# ControllerV1.net
KiCad netlist of a schematic drawn in Altium Designer
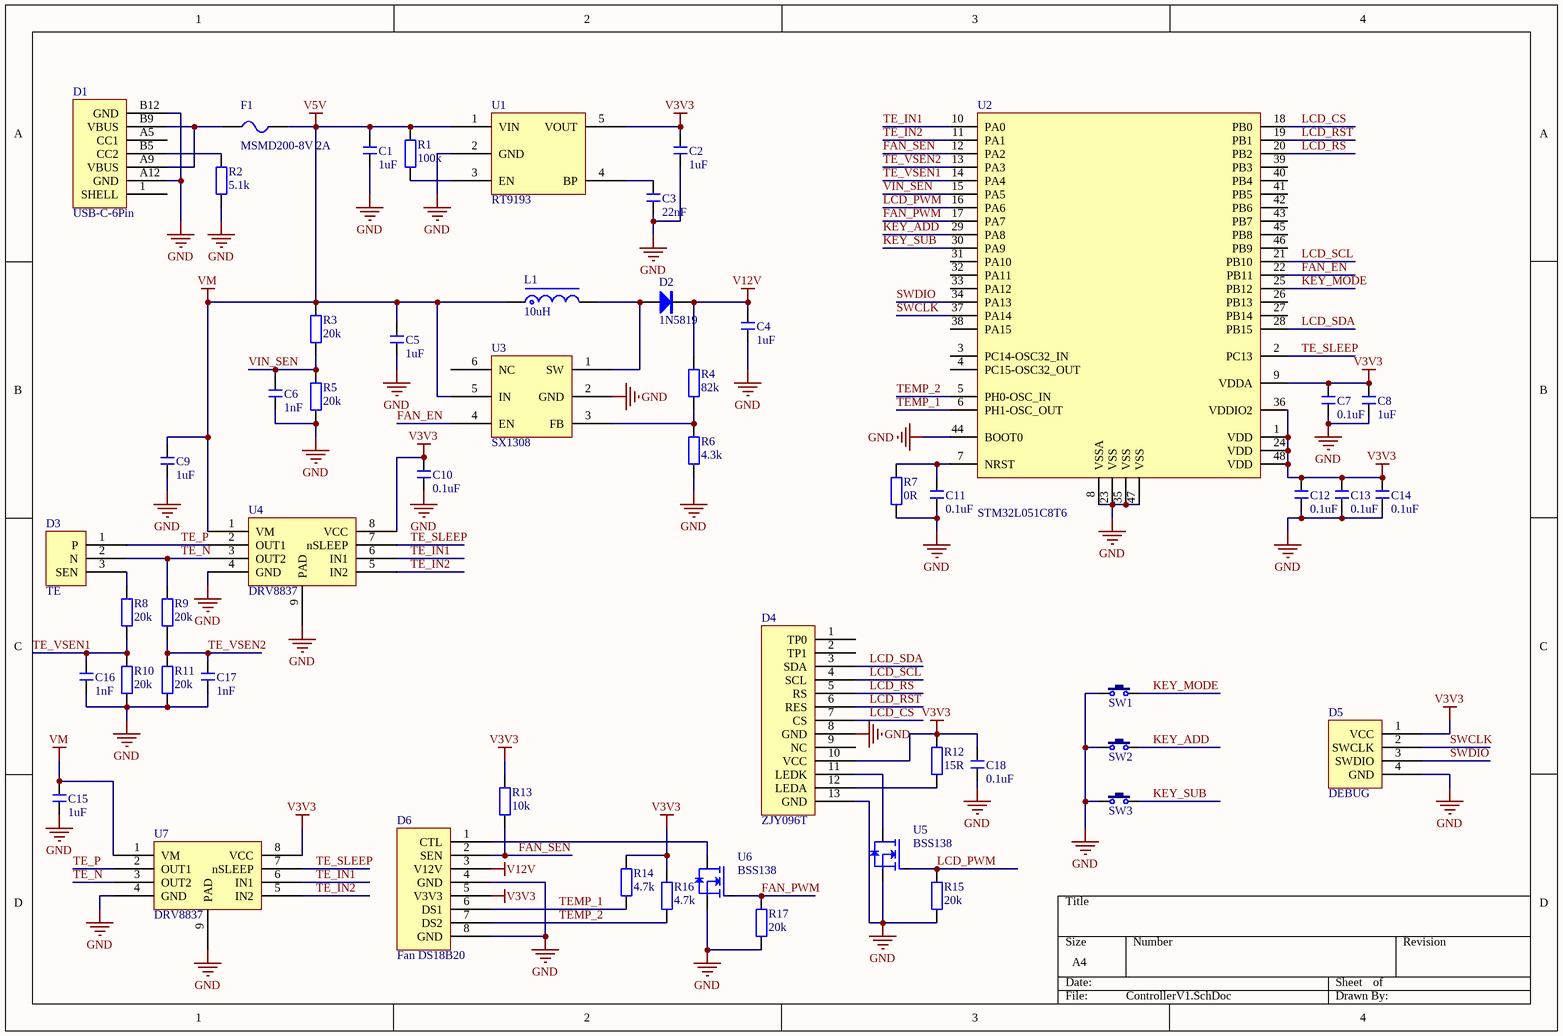
[diagram p0: ControllerV1.SchDoc]

(export (version "E")
  (design (tool "Eeschema 10.0.6"))
  (components
    (comp (ref "C1")
      (value "1uF")
      (footprint "C 0603_L")
      (description "无极性贴片电容")
      (fields (field (name "版权归属") "源创客"))
      (libsource (lib "3.1   - 电阻-电容-电感") (part "C"))
    )
    (comp (ref "C2")
      (value "1uF")
      (footprint "C 0603_L")
      (description "无极性贴片电容")
      (fields (field (name "版权归属") "源创客"))
      (libsource (lib "3.1   - 电阻-电容-电感") (part "C"))
    )
    (comp (ref "C3")
      (value "22nF")
      (footprint "C 0603_L")
      (description "无极性贴片电容")
      (fields (field (name "版权归属") "源创客"))
      (libsource (lib "3.1   - 电阻-电容-电感") (part "C"))
    )
    (comp (ref "C4")
      (value "1uF")
      (footprint "C 0603_L")
      (description "无极性贴片电容")
      (fields (field (name "版权归属") "源创客"))
      (libsource (lib "3.1   - 电阻-电容-电感") (part "C"))
    )
    (comp (ref "C5")
      (value "1uF")
      (footprint "C 0603_L")
      (description "无极性贴片电容")
      (fields (field (name "版权归属") "源创客"))
      (libsource (lib "3.1   - 电阻-电容-电感") (part "C"))
    )
    (comp (ref "C6")
      (value "1nF")
      (footprint "C 0603_L")
      (description "无极性贴片电容")
      (fields (field (name "版权归属") "源创客"))
      (libsource (lib "3.1   - 电阻-电容-电感") (part "C"))
    )
    (comp (ref "C7")
      (value "0.1uF")
      (footprint "C 0603_L")
      (description "无极性贴片电容")
      (fields (field (name "版权归属") "源创客"))
      (libsource (lib "3.1   - 电阻-电容-电感") (part "C"))
    )
    (comp (ref "C8")
      (value "1uF")
      (footprint "C 0603_L")
      (description "无极性贴片电容")
      (fields (field (name "版权归属") "源创客"))
      (libsource (lib "3.1   - 电阻-电容-电感") (part "C"))
    )
    (comp (ref "C9")
      (value "1uF")
      (footprint "C 0603_L")
      (description "无极性贴片电容")
      (fields (field (name "版权归属") "源创客"))
      (libsource (lib "3.1   - 电阻-电容-电感") (part "C"))
    )
    (comp (ref "C10")
      (value "0.1uF")
      (footprint "C 0603_L")
      (description "无极性贴片电容")
      (fields (field (name "版权归属") "源创客"))
      (libsource (lib "3.1   - 电阻-电容-电感") (part "C"))
    )
    (comp (ref "C11")
      (value "0.1uF")
      (footprint "C 0603_L")
      (description "无极性贴片电容")
      (fields (field (name "版权归属") "源创客"))
      (libsource (lib "3.1   - 电阻-电容-电感") (part "C"))
    )
    (comp (ref "C12")
      (value "0.1uF")
      (footprint "C 0603_L")
      (description "无极性贴片电容")
      (fields (field (name "版权归属") "源创客"))
      (libsource (lib "3.1   - 电阻-电容-电感") (part "C"))
    )
    (comp (ref "C13")
      (value "0.1uF")
      (footprint "C 0603_L")
      (description "无极性贴片电容")
      (fields (field (name "版权归属") "源创客"))
      (libsource (lib "3.1   - 电阻-电容-电感") (part "C"))
    )
    (comp (ref "C14")
      (value "0.1uF")
      (footprint "C 0603_L")
      (description "无极性贴片电容")
      (fields (field (name "版权归属") "源创客"))
      (libsource (lib "3.1   - 电阻-电容-电感") (part "C"))
    )
    (comp (ref "C15")
      (value "1uF")
      (footprint "C 0603_L")
      (description "无极性贴片电容")
      (fields (field (name "版权归属") "源创客"))
      (libsource (lib "3.1   - 电阻-电容-电感") (part "C"))
    )
    (comp (ref "C16")
      (value "1nF")
      (footprint "C 0603_L")
      (description "无极性贴片电容")
      (fields (field (name "版权归属") "源创客"))
      (libsource (lib "3.1   - 电阻-电容-电感") (part "C"))
    )
    (comp (ref "C17")
      (value "1nF")
      (footprint "C 0603_L")
      (description "无极性贴片电容")
      (fields (field (name "版权归属") "源创客"))
      (libsource (lib "3.1   - 电阻-电容-电感") (part "C"))
    )
    (comp (ref "C18")
      (value "0.1uF")
      (footprint "C 0603_L")
      (description "无极性贴片电容")
      (fields (field (name "版权归属") "源创客"))
      (libsource (lib "3.1   - 电阻-电容-电感") (part "C"))
    )
    (comp (ref "D1")
      (value "USB-C-6Pin")
      (footprint "USB-C-6Pin-InBoard")
      (libsource (lib "AlPcb") (part "USB-C-6Pin"))
    )
    (comp (ref "D2")
      (value "1N5819")
      (footprint "SOD-323")
      (description "肖特基二极管")
      (fields (field (name "版权归属") "源创客"))
      (libsource (lib "8.1   - 二极管-整流桥") (part "1N5819"))
    )
    (comp (ref "D3") (value "TE") (footprint "TE") (libsource (lib "ThermosCupLib") (part "TE")))
    (comp (ref "D4")
      (value "ZJY096T")
      (footprint "LCD_0p96_ZJY096T")
      (libsource (lib "AlPcb") (part "LCD_0p96_ZJY096T"))
    )
    (comp (ref "D5") (value "DEBUG") (footprint "DBG") (libsource (lib "ThermosCupLib") (part "DBG")))
    (comp (ref "D6")
      (value "Fan DS18B20")
      (footprint "Connector Fan DS18B20")
      (libsource (lib "ThermosCupLib") (part "Connecter Fan DS18B20"))
    )
    (comp (ref "F1")
      (value "MSMD200-8V 2A")
      (footprint "FU 1206")
      (description "贴片保险丝")
      (fields (field (name "版权归属") "源创客"))
      (libsource (lib "保险丝-晶振") (part "FU"))
    )
    (comp (ref "L1")
      (value "10uH")
      (footprint "NR4020")
      (description "NR磁胶电感")
      (fields (field (name "版权归属") "源创客"))
      (libsource (lib "3.1   - 电阻-电容-电感") (part "L-NR"))
    )
    (comp (ref "R1")
      (value "100k")
      (footprint "R 0603_L")
      (description "贴片电阻")
      (fields (field (name "版权归属") "源创客"))
      (libsource (lib "3.1   - 电阻-电容-电感") (part "R"))
    )
    (comp (ref "R2")
      (value "5.1k")
      (footprint "R 0603_L")
      (description "贴片电阻")
      (fields (field (name "版权归属") "源创客"))
      (libsource (lib "3.1   - 电阻-电容-电感") (part "R"))
    )
    (comp (ref "R3")
      (value "20k")
      (footprint "R 0603_L")
      (description "贴片电阻")
      (fields (field (name "版权归属") "源创客"))
      (libsource (lib "3.1   - 电阻-电容-电感") (part "R"))
    )
    (comp (ref "R4")
      (value "82k")
      (footprint "R 0603_L")
      (description "贴片电阻")
      (fields (field (name "版权归属") "源创客"))
      (libsource (lib "3.1   - 电阻-电容-电感") (part "R"))
    )
    (comp (ref "R5")
      (value "20k")
      (footprint "R 0603_L")
      (description "贴片电阻")
      (fields (field (name "版权归属") "源创客"))
      (libsource (lib "3.1   - 电阻-电容-电感") (part "R"))
    )
    (comp (ref "R6")
      (value "4.3k")
      (footprint "R 0603_L")
      (description "贴片电阻")
      (fields (field (name "版权归属") "源创客"))
      (libsource (lib "3.1   - 电阻-电容-电感") (part "R"))
    )
    (comp (ref "R7")
      (value "0R")
      (footprint "R 0603_L")
      (description "贴片电阻")
      (fields (field (name "版权归属") "源创客"))
      (libsource (lib "3.1   - 电阻-电容-电感") (part "R"))
    )
    (comp (ref "R8")
      (value "20k")
      (footprint "R 0603_L")
      (description "贴片电阻")
      (fields (field (name "版权归属") "源创客"))
      (libsource (lib "3.1   - 电阻-电容-电感") (part "R"))
    )
    (comp (ref "R9")
      (value "20k")
      (footprint "R 0603_L")
      (description "贴片电阻")
      (fields (field (name "版权归属") "源创客"))
      (libsource (lib "3.1   - 电阻-电容-电感") (part "R"))
    )
    (comp (ref "R10")
      (value "20k")
      (footprint "R 0603_L")
      (description "贴片电阻")
      (fields (field (name "版权归属") "源创客"))
      (libsource (lib "3.1   - 电阻-电容-电感") (part "R"))
    )
    (comp (ref "R11")
      (value "20k")
      (footprint "R 0603_L")
      (description "贴片电阻")
      (fields (field (name "版权归属") "源创客"))
      (libsource (lib "3.1   - 电阻-电容-电感") (part "R"))
    )
    (comp (ref "R12")
      (value "15R")
      (footprint "R 0603_L")
      (description "贴片电阻")
      (fields (field (name "版权归属") "源创客"))
      (libsource (lib "3.1   - 电阻-电容-电感") (part "R"))
    )
    (comp (ref "R13")
      (value "10k")
      (footprint "R 0603_L")
      (description "贴片电阻")
      (fields (field (name "版权归属") "源创客"))
      (libsource (lib "3.1   - 电阻-电容-电感") (part "R"))
    )
    (comp (ref "R14")
      (value "4.7k")
      (footprint "R 0603_L")
      (description "贴片电阻")
      (fields (field (name "版权归属") "源创客"))
      (libsource (lib "3.1   - 电阻-电容-电感") (part "R"))
    )
    (comp (ref "R15")
      (value "20k")
      (footprint "R 0603_L")
      (description "贴片电阻")
      (fields (field (name "版权归属") "源创客"))
      (libsource (lib "3.1   - 电阻-电容-电感") (part "R"))
    )
    (comp (ref "R16")
      (value "4.7k")
      (footprint "R 0603_L")
      (description "贴片电阻")
      (fields (field (name "版权归属") "源创客"))
      (libsource (lib "3.1   - 电阻-电容-电感") (part "R"))
    )
    (comp (ref "R17")
      (value "20k")
      (footprint "R 0603_L")
      (description "贴片电阻")
      (fields (field (name "版权归属") "源创客"))
      (libsource (lib "3.1   - 电阻-电容-电感") (part "R"))
    )
    (comp (ref "SW1")
      (value "3x6x5")
      (footprint "TSW SMD-3*6*5")
      (description "3x6轻触开关")
      (fields (field (name "版权归属") "源创客"))
      (libsource (lib "5.1   - 按键-开关") (part "TSW 3x6"))
    )
    (comp (ref "SW2")
      (value "3x6x5")
      (footprint "TSW SMD-3*6*5")
      (description "3x6轻触开关")
      (fields (field (name "版权归属") "源创客"))
      (libsource (lib "5.1   - 按键-开关") (part "TSW 3x6"))
    )
    (comp (ref "SW3")
      (value "3x6x5")
      (footprint "TSW SMD-3*6*5")
      (description "3x6轻触开关")
      (fields (field (name "版权归属") "源创客"))
      (libsource (lib "5.1   - 按键-开关") (part "TSW 3x6"))
    )
    (comp (ref "U1") (value "RT9193") (footprint "SOT23-5 RT9193") (libsource (lib "AlPcb") (part "RT9193")))
    (comp (ref "U2")
      (value "STM32L051C8T6")
      (footprint "LQFP48")
      (libsource (lib "AlPcb") (part "STM32L051C8T6"))
    )
    (comp (ref "U3") (value "SX1308") (footprint "SOT23-6 SX1308") (libsource (lib "AlPcb") (part "SX1308")))
    (comp (ref "U4")
      (value "DRV8837")
      (footprint "WSON-8 DRV8837")
      (libsource (lib "AlPcb") (part "DRV8837"))
    )
    (comp (ref "U5") (value "BSS138") (footprint "SOT23-3 BSS138") (libsource (lib "AlPcb") (part "BSS138")))
    (comp (ref "U6") (value "BSS138") (footprint "SOT23-3 BSS138") (libsource (lib "AlPcb") (part "BSS138")))
    (comp (ref "U7")
      (value "DRV8837")
      (footprint "WSON-8 DRV8837")
      (libsource (lib "AlPcb") (part "DRV8837"))
    )
  )
  (nets
    (net (code "1") (name "/FAN_EN") (class "Default")
      (node (ref "U2") (pin "22") (pinfunction "PB11_22") (pintype "passive"))
      (node (ref "U3") (pin "4") (pinfunction "EN_4") (pintype "passive"))
    )
    (net (code "2") (name "/FAN_PWM") (class "Default")
      (node (ref "R17") (pin "2") (pinfunction "2_2") (pintype "passive"))
      (node (ref "U2") (pin "17") (pinfunction "PA7_17") (pintype "passive"))
      (node (ref "U6") (pin "1") (pinfunction "G_1") (pintype "passive"))
    )
    (net (code "3") (name "/FAN_SEN") (class "Default")
      (node (ref "D6") (pin "2") (pinfunction "SEN_2") (pintype "passive"))
      (node (ref "R13") (pin "1") (pinfunction "1_1") (pintype "passive"))
      (node (ref "U2") (pin "12") (pinfunction "PA2_12") (pintype "passive"))
    )
    (net (code "4") (name "/KEY_ADD") (class "Default")
      (node (ref "SW2") (pin "2") (pinfunction "2_2") (pintype "passive"))
      (node (ref "U2") (pin "29") (pinfunction "PA8_29") (pintype "passive"))
    )
    (net (code "5") (name "/KEY_MODE") (class "Default")
      (node (ref "SW1") (pin "2") (pinfunction "2_2") (pintype "passive"))
      (node (ref "U2") (pin "25") (pinfunction "PB12_25") (pintype "passive"))
    )
    (net (code "6") (name "/KEY_SUB") (class "Default")
      (node (ref "SW3") (pin "2") (pinfunction "2_2") (pintype "passive"))
      (node (ref "U2") (pin "30") (pinfunction "PA9_30") (pintype "passive"))
    )
    (net (code "7") (name "/LCD_CS") (class "Default")
      (node (ref "D4") (pin "7") (pinfunction "CS_7") (pintype "passive"))
      (node (ref "U2") (pin "18") (pinfunction "PB0_18") (pintype "passive"))
    )
    (net (code "8") (name "/LCD_PWM") (class "Default")
      (node (ref "R15") (pin "2") (pinfunction "2_2") (pintype "passive"))
      (node (ref "U2") (pin "16") (pinfunction "PA6_16") (pintype "passive"))
      (node (ref "U5") (pin "1") (pinfunction "G_1") (pintype "passive"))
    )
    (net (code "9") (name "/LCD_RS") (class "Default")
      (node (ref "D4") (pin "5") (pinfunction "RS_5") (pintype "passive"))
      (node (ref "U2") (pin "20") (pinfunction "PB2_20") (pintype "passive"))
    )
    (net (code "10") (name "/LCD_RST") (class "Default")
      (node (ref "D4") (pin "6") (pinfunction "RES_6") (pintype "passive"))
      (node (ref "U2") (pin "19") (pinfunction "PB1_19") (pintype "passive"))
    )
    (net (code "11") (name "/LCD_SCL") (class "Default")
      (node (ref "D4") (pin "4") (pinfunction "SCL_4") (pintype "passive"))
      (node (ref "U2") (pin "21") (pinfunction "PB10_21") (pintype "passive"))
    )
    (net (code "12") (name "/LCD_SDA") (class "Default")
      (node (ref "D4") (pin "3") (pinfunction "SDA_3") (pintype "passive"))
      (node (ref "U2") (pin "28") (pinfunction "PB15_28") (pintype "passive"))
    )
    (net (code "13") (name "/SWCLK") (class "Default")
      (node (ref "D5") (pin "2") (pinfunction "SWCLK_2") (pintype "passive"))
      (node (ref "U2") (pin "37") (pinfunction "PA14_37") (pintype "passive"))
    )
    (net (code "14") (name "/SWDIO") (class "Default")
      (node (ref "D5") (pin "3") (pinfunction "SWDIO_3") (pintype "passive"))
      (node (ref "U2") (pin "34") (pinfunction "PA13_34") (pintype "passive"))
    )
    (net (code "15") (name "/TEMP_1") (class "Default")
      (node (ref "D6") (pin "6") (pinfunction "DS1_6") (pintype "passive"))
      (node (ref "R14") (pin "1") (pinfunction "1_1") (pintype "passive"))
      (node (ref "U2") (pin "6") (pinfunction "PH1-OSC_OUT_6") (pintype "passive"))
    )
    (net (code "16") (name "/TEMP_2") (class "Default")
      (node (ref "D6") (pin "7") (pinfunction "DS2_7") (pintype "passive"))
      (node (ref "R16") (pin "1") (pinfunction "1_1") (pintype "passive"))
      (node (ref "U2") (pin "5") (pinfunction "PH0-OSC_IN_5") (pintype "passive"))
    )
    (net (code "17") (name "/TE_IN1") (class "Default")
      (node (ref "U2") (pin "10") (pinfunction "PA0_10") (pintype "passive"))
      (node (ref "U4") (pin "6") (pinfunction "IN1_6") (pintype "passive"))
      (node (ref "U7") (pin "6") (pinfunction "IN1_6") (pintype "passive"))
    )
    (net (code "18") (name "/TE_IN2") (class "Default")
      (node (ref "U2") (pin "11") (pinfunction "PA1_11") (pintype "passive"))
      (node (ref "U4") (pin "5") (pinfunction "IN2_5") (pintype "passive"))
      (node (ref "U7") (pin "5") (pinfunction "IN2_5") (pintype "passive"))
    )
    (net (code "19") (name "/TE_N") (class "Default")
      (node (ref "D3") (pin "2") (pinfunction "N_2") (pintype "passive"))
      (node (ref "R9") (pin "2") (pinfunction "2_2") (pintype "passive"))
      (node (ref "U4") (pin "3") (pinfunction "OUT2_3") (pintype "passive"))
      (node (ref "U7") (pin "3") (pinfunction "OUT2_3") (pintype "passive"))
    )
    (net (code "20") (name "/TE_P") (class "Default")
      (node (ref "D3") (pin "1") (pinfunction "P_1") (pintype "passive"))
      (node (ref "U4") (pin "2") (pinfunction "OUT1_2") (pintype "passive"))
      (node (ref "U7") (pin "2") (pinfunction "OUT1_2") (pintype "passive"))
    )
    (net (code "21") (name "/TE_SLEEP") (class "Default")
      (node (ref "U2") (pin "2") (pinfunction "PC13_2") (pintype "passive"))
      (node (ref "U4") (pin "7") (pinfunction "nSLEEP_7") (pintype "passive"))
      (node (ref "U7") (pin "7") (pinfunction "nSLEEP_7") (pintype "passive"))
    )
    (net (code "22") (name "/TE_VSEN1") (class "Default")
      (node (ref "C16") (pin "2") (pinfunction "2_2") (pintype "passive"))
      (node (ref "R10") (pin "2") (pinfunction "2_2") (pintype "passive"))
      (node (ref "R8") (pin "1") (pinfunction "1_1") (pintype "passive"))
      (node (ref "U2") (pin "14") (pinfunction "PA4_14") (pintype "passive"))
    )
    (net (code "23") (name "/TE_VSEN2") (class "Default")
      (node (ref "C17") (pin "2") (pinfunction "2_2") (pintype "passive"))
      (node (ref "R11") (pin "2") (pinfunction "2_2") (pintype "passive"))
      (node (ref "R9") (pin "1") (pinfunction "1_1") (pintype "passive"))
      (node (ref "U2") (pin "13") (pinfunction "PA3_13") (pintype "passive"))
    )
    (net (code "24") (name "/VIN_SEN") (class "Default")
      (node (ref "C6") (pin "2") (pinfunction "2_2") (pintype "passive"))
      (node (ref "R3") (pin "1") (pinfunction "1_1") (pintype "passive"))
      (node (ref "R5") (pin "2") (pinfunction "2_2") (pintype "passive"))
      (node (ref "U2") (pin "15") (pinfunction "PA5_15") (pintype "passive"))
    )
    (net (code "25") (name "GND") (class "Default")
      (node (ref "C1") (pin "1") (pinfunction "1_1") (pintype "passive"))
      (node (ref "C10") (pin "1") (pinfunction "1_1") (pintype "passive"))
      (node (ref "C11") (pin "1") (pinfunction "1_1") (pintype "passive"))
      (node (ref "C12") (pin "1") (pinfunction "1_1") (pintype "passive"))
      (node (ref "C13") (pin "1") (pinfunction "1_1") (pintype "passive"))
      (node (ref "C14") (pin "1") (pinfunction "1_1") (pintype "passive"))
      (node (ref "C15") (pin "1") (pinfunction "1_1") (pintype "passive"))
      (node (ref "C16") (pin "1") (pinfunction "1_1") (pintype "passive"))
      (node (ref "C17") (pin "1") (pinfunction "1_1") (pintype "passive"))
      (node (ref "C18") (pin "1") (pinfunction "1_1") (pintype "passive"))
      (node (ref "C2") (pin "1") (pinfunction "1_1") (pintype "passive"))
      (node (ref "C3") (pin "1") (pinfunction "1_1") (pintype "passive"))
      (node (ref "C4") (pin "1") (pinfunction "1_1") (pintype "passive"))
      (node (ref "C5") (pin "1") (pinfunction "1_1") (pintype "passive"))
      (node (ref "C6") (pin "1") (pinfunction "1_1") (pintype "passive"))
      (node (ref "C7") (pin "1") (pinfunction "1_1") (pintype "passive"))
      (node (ref "C8") (pin "1") (pinfunction "1_1") (pintype "passive"))
      (node (ref "C9") (pin "1") (pinfunction "1_1") (pintype "passive"))
      (node (ref "D1") (pin "A12") (pinfunction "GND_A12") (pintype "passive"))
      (node (ref "D1") (pin "B12") (pinfunction "GND_B12") (pintype "passive"))
      (node (ref "D4") (pin "13") (pinfunction "GND_13") (pintype "passive"))
      (node (ref "D4") (pin "8") (pinfunction "GND_8") (pintype "passive"))
      (node (ref "D5") (pin "4") (pinfunction "GND_4") (pintype "passive"))
      (node (ref "D6") (pin "4") (pinfunction "GND_4") (pintype "passive"))
      (node (ref "D6") (pin "8") (pinfunction "GND_8") (pintype "passive"))
      (node (ref "R10") (pin "1") (pinfunction "1_1") (pintype "passive"))
      (node (ref "R11") (pin "1") (pinfunction "1_1") (pintype "passive"))
      (node (ref "R15") (pin "1") (pinfunction "1_1") (pintype "passive"))
      (node (ref "R17") (pin "1") (pinfunction "1_1") (pintype "passive"))
      (node (ref "R2") (pin "1") (pinfunction "1_1") (pintype "passive"))
      (node (ref "R5") (pin "1") (pinfunction "1_1") (pintype "passive"))
      (node (ref "R6") (pin "1") (pinfunction "1_1") (pintype "passive"))
      (node (ref "R7") (pin "1") (pinfunction "1_1") (pintype "passive"))
      (node (ref "SW1") (pin "1") (pinfunction "1_1") (pintype "passive"))
      (node (ref "SW2") (pin "1") (pinfunction "1_1") (pintype "passive"))
      (node (ref "SW3") (pin "1") (pinfunction "1_1") (pintype "passive"))
      (node (ref "U1") (pin "2") (pinfunction "GND_2") (pintype "passive"))
      (node (ref "U2") (pin "23") (pinfunction "VSS_23") (pintype "passive"))
      (node (ref "U2") (pin "35") (pinfunction "VSS_35") (pintype "passive"))
      (node (ref "U2") (pin "44") (pinfunction "BOOT0_44") (pintype "passive"))
      (node (ref "U2") (pin "47") (pinfunction "VSS_47") (pintype "passive"))
      (node (ref "U2") (pin "8") (pinfunction "VSSA_8") (pintype "passive"))
      (node (ref "U3") (pin "2") (pinfunction "GND_2") (pintype "passive"))
      (node (ref "U4") (pin "4") (pinfunction "GND_4") (pintype "passive"))
      (node (ref "U4") (pin "9") (pinfunction "PAD_9") (pintype "passive"))
      (node (ref "U5") (pin "2") (pinfunction "S_2") (pintype "passive"))
      (node (ref "U6") (pin "2") (pinfunction "S_2") (pintype "passive"))
      (node (ref "U7") (pin "4") (pinfunction "GND_4") (pintype "passive"))
      (node (ref "U7") (pin "9") (pinfunction "PAD_9") (pintype "passive"))
    )
    (net (code "26") (name "Net-(D1-CC2)") (class "Default")
      (node (ref "D1") (pin "B5") (pinfunction "CC2_B5") (pintype "passive"))
      (node (ref "R2") (pin "2") (pinfunction "2_2") (pintype "passive"))
    )
    (net (code "27") (name "Net-(D1-VBUS-PadA9)") (class "Default")
      (node (ref "D1") (pin "A9") (pinfunction "VBUS_A9") (pintype "passive"))
      (node (ref "D1") (pin "B9") (pinfunction "VBUS_B9") (pintype "passive"))
      (node (ref "F1") (pin "1") (pinfunction "1_1") (pintype "passive"))
    )
    (net (code "28") (name "Net-(D2-A)") (class "Default")
      (node (ref "D2") (pin "1") (pinfunction "A_1") (pintype "passive"))
      (node (ref "L1") (pin "2") (pinfunction "2_2") (pintype "passive"))
      (node (ref "U3") (pin "1") (pinfunction "SW_1") (pintype "passive"))
    )
    (net (code "29") (name "Net-(D3-SEN)") (class "Default")
      (node (ref "D3") (pin "3") (pinfunction "SEN_3") (pintype "passive"))
      (node (ref "R8") (pin "2") (pinfunction "2_2") (pintype "passive"))
    )
    (net (code "30") (name "Net-(D4-LEDA)") (class "Default")
      (node (ref "D4") (pin "12") (pinfunction "LEDA_12") (pintype "passive"))
      (node (ref "R12") (pin "1") (pinfunction "1_1") (pintype "passive"))
    )
    (net (code "31") (name "Net-(D4-LEDK)") (class "Default")
      (node (ref "D4") (pin "11") (pinfunction "LEDK_11") (pintype "passive"))
      (node (ref "U5") (pin "3") (pinfunction "D_3") (pintype "passive"))
    )
    (net (code "32") (name "Net-(D6-CTL)") (class "Default")
      (node (ref "D6") (pin "1") (pinfunction "CTL_1") (pintype "passive"))
      (node (ref "U6") (pin "3") (pinfunction "D_3") (pintype "passive"))
    )
    (net (code "33") (name "Net-(U1-BP)") (class "Default")
      (node (ref "C3") (pin "2") (pinfunction "2_2") (pintype "passive"))
      (node (ref "U1") (pin "4") (pinfunction "BP_4") (pintype "passive"))
    )
    (net (code "34") (name "Net-(U1-EN)") (class "Default")
      (node (ref "R1") (pin "1") (pinfunction "1_1") (pintype "passive"))
      (node (ref "U1") (pin "3") (pinfunction "EN_3") (pintype "passive"))
    )
    (net (code "35") (name "Net-(U2-NRST)") (class "Default")
      (node (ref "C11") (pin "2") (pinfunction "2_2") (pintype "passive"))
      (node (ref "R7") (pin "2") (pinfunction "2_2") (pintype "passive"))
      (node (ref "U2") (pin "7") (pinfunction "NRST_7") (pintype "passive"))
    )
    (net (code "36") (name "Net-(U3-FB)") (class "Default")
      (node (ref "R4") (pin "1") (pinfunction "1_1") (pintype "passive"))
      (node (ref "R6") (pin "2") (pinfunction "2_2") (pintype "passive"))
      (node (ref "U3") (pin "3") (pinfunction "FB_3") (pintype "passive"))
    )
    (net (code "37") (name "V3V3") (class "Default")
      (node (ref "C10") (pin "2") (pinfunction "2_2") (pintype "passive"))
      (node (ref "C12") (pin "2") (pinfunction "2_2") (pintype "passive"))
      (node (ref "C13") (pin "2") (pinfunction "2_2") (pintype "passive"))
      (node (ref "C14") (pin "2") (pinfunction "2_2") (pintype "passive"))
      (node (ref "C18") (pin "2") (pinfunction "2_2") (pintype "passive"))
      (node (ref "C2") (pin "2") (pinfunction "2_2") (pintype "passive"))
      (node (ref "C7") (pin "2") (pinfunction "2_2") (pintype "passive"))
      (node (ref "C8") (pin "2") (pinfunction "2_2") (pintype "passive"))
      (node (ref "D4") (pin "10") (pinfunction "VCC_10") (pintype "passive"))
      (node (ref "D5") (pin "1") (pinfunction "VCC_1") (pintype "passive"))
      (node (ref "D6") (pin "5") (pinfunction "V3V3_5") (pintype "passive"))
      (node (ref "R12") (pin "2") (pinfunction "2_2") (pintype "passive"))
      (node (ref "R13") (pin "2") (pinfunction "2_2") (pintype "passive"))
      (node (ref "R14") (pin "2") (pinfunction "2_2") (pintype "passive"))
      (node (ref "R16") (pin "2") (pinfunction "2_2") (pintype "passive"))
      (node (ref "U1") (pin "5") (pinfunction "VOUT_5") (pintype "passive"))
      (node (ref "U2") (pin "1") (pinfunction "VDD_1") (pintype "passive"))
      (node (ref "U2") (pin "24") (pinfunction "VDD_24") (pintype "passive"))
      (node (ref "U2") (pin "36") (pinfunction "VDDIO2_36") (pintype "passive"))
      (node (ref "U2") (pin "48") (pinfunction "VDD_48") (pintype "passive"))
      (node (ref "U2") (pin "9") (pinfunction "VDDA_9") (pintype "passive"))
      (node (ref "U4") (pin "8") (pinfunction "VCC_8") (pintype "passive"))
      (node (ref "U7") (pin "8") (pinfunction "VCC_8") (pintype "passive"))
    )
    (net (code "38") (name "V5V") (class "Default")
      (node (ref "C1") (pin "2") (pinfunction "2_2") (pintype "passive"))
      (node (ref "C15") (pin "2") (pinfunction "2_2") (pintype "passive"))
      (node (ref "C5") (pin "2") (pinfunction "2_2") (pintype "passive"))
      (node (ref "C9") (pin "2") (pinfunction "2_2") (pintype "passive"))
      (node (ref "F1") (pin "2") (pinfunction "2_2") (pintype "passive"))
      (node (ref "L1") (pin "1") (pinfunction "1_1") (pintype "passive"))
      (node (ref "R1") (pin "2") (pinfunction "2_2") (pintype "passive"))
      (node (ref "R3") (pin "2") (pinfunction "2_2") (pintype "passive"))
      (node (ref "U1") (pin "1") (pinfunction "VIN_1") (pintype "passive"))
      (node (ref "U3") (pin "5") (pinfunction "IN_5") (pintype "passive"))
      (node (ref "U4") (pin "1") (pinfunction "VM_1") (pintype "passive"))
      (node (ref "U7") (pin "1") (pinfunction "VM_1") (pintype "passive"))
    )
    (net (code "39") (name "V12V") (class "Default")
      (node (ref "C4") (pin "2") (pinfunction "2_2") (pintype "passive"))
      (node (ref "D2") (pin "2") (pinfunction "K_2") (pintype "passive"))
      (node (ref "D6") (pin "3") (pinfunction "V12V_3") (pintype "passive"))
      (node (ref "R4") (pin "2") (pinfunction "2_2") (pintype "passive"))
    )
    (net (code "40") (name "unconnected-(D1-CC1-PadA5)") (class "Default")
      (node (ref "D1") (pin "A5") (pinfunction "CC1_A5") (pintype "passive"))
    )
    (net (code "41") (name "unconnected-(D1-SHELL-Pad1)") (class "Default")
      (node (ref "D1") (pin "1") (pinfunction "SHELL_1") (pintype "passive"))
    )
    (net (code "42") (name "unconnected-(D4-NC-Pad9)") (class "Default")
      (node (ref "D4") (pin "9") (pinfunction "NC_9") (pintype "passive"))
    )
    (net (code "43") (name "unconnected-(D4-TP0-Pad1)") (class "Default")
      (node (ref "D4") (pin "1") (pinfunction "TP0_1") (pintype "passive"))
    )
    (net (code "44") (name "unconnected-(D4-TP1-Pad2)") (class "Default")
      (node (ref "D4") (pin "2") (pinfunction "TP1_2") (pintype "passive"))
    )
    (net (code "45") (name "unconnected-(U2-PA10-Pad31)") (class "Default")
      (node (ref "U2") (pin "31") (pinfunction "PA10_31") (pintype "passive"))
    )
    (net (code "46") (name "unconnected-(U2-PA11-Pad32)") (class "Default")
      (node (ref "U2") (pin "32") (pinfunction "PA11_32") (pintype "passive"))
    )
    (net (code "47") (name "unconnected-(U2-PA12-Pad33)") (class "Default")
      (node (ref "U2") (pin "33") (pinfunction "PA12_33") (pintype "passive"))
    )
    (net (code "48") (name "unconnected-(U2-PA15-Pad38)") (class "Default")
      (node (ref "U2") (pin "38") (pinfunction "PA15_38") (pintype "passive"))
    )
    (net (code "49") (name "unconnected-(U2-PB3-Pad39)") (class "Default")
      (node (ref "U2") (pin "39") (pinfunction "PB3_39") (pintype "passive"))
    )
    (net (code "50") (name "unconnected-(U2-PB4-Pad40)") (class "Default")
      (node (ref "U2") (pin "40") (pinfunction "PB4_40") (pintype "passive"))
    )
    (net (code "51") (name "unconnected-(U2-PB5-Pad41)") (class "Default")
      (node (ref "U2") (pin "41") (pinfunction "PB5_41") (pintype "passive"))
    )
    (net (code "52") (name "unconnected-(U2-PB6-Pad42)") (class "Default")
      (node (ref "U2") (pin "42") (pinfunction "PB6_42") (pintype "passive"))
    )
    (net (code "53") (name "unconnected-(U2-PB7-Pad43)") (class "Default")
      (node (ref "U2") (pin "43") (pinfunction "PB7_43") (pintype "passive"))
    )
    (net (code "54") (name "unconnected-(U2-PB8-Pad45)") (class "Default")
      (node (ref "U2") (pin "45") (pinfunction "PB8_45") (pintype "passive"))
    )
    (net (code "55") (name "unconnected-(U2-PB9-Pad46)") (class "Default")
      (node (ref "U2") (pin "46") (pinfunction "PB9_46") (pintype "passive"))
    )
    (net (code "56") (name "unconnected-(U2-PB13-Pad26)") (class "Default")
      (node (ref "U2") (pin "26") (pinfunction "PB13_26") (pintype "passive"))
    )
    (net (code "57") (name "unconnected-(U2-PB14-Pad27)") (class "Default")
      (node (ref "U2") (pin "27") (pinfunction "PB14_27") (pintype "passive"))
    )
    (net (code "58") (name "unconnected-(U2-PC14-OSC32_IN-Pad3)") (class "Default")
      (node (ref "U2") (pin "3") (pinfunction "PC14-OSC32_IN_3") (pintype "passive"))
    )
    (net (code "59") (name "unconnected-(U2-PC15-OSC32_OUT-Pad4)") (class "Default")
      (node (ref "U2") (pin "4") (pinfunction "PC15-OSC32_OUT_4") (pintype "passive"))
    )
    (net (code "60") (name "unconnected-(U3-NC-Pad6)") (class "Default")
      (node (ref "U3") (pin "6") (pinfunction "NC_6") (pintype "passive"))
    )
  )
)
